# deadlocks3.net
KiCad netlist of a schematic drawn in EAGLE
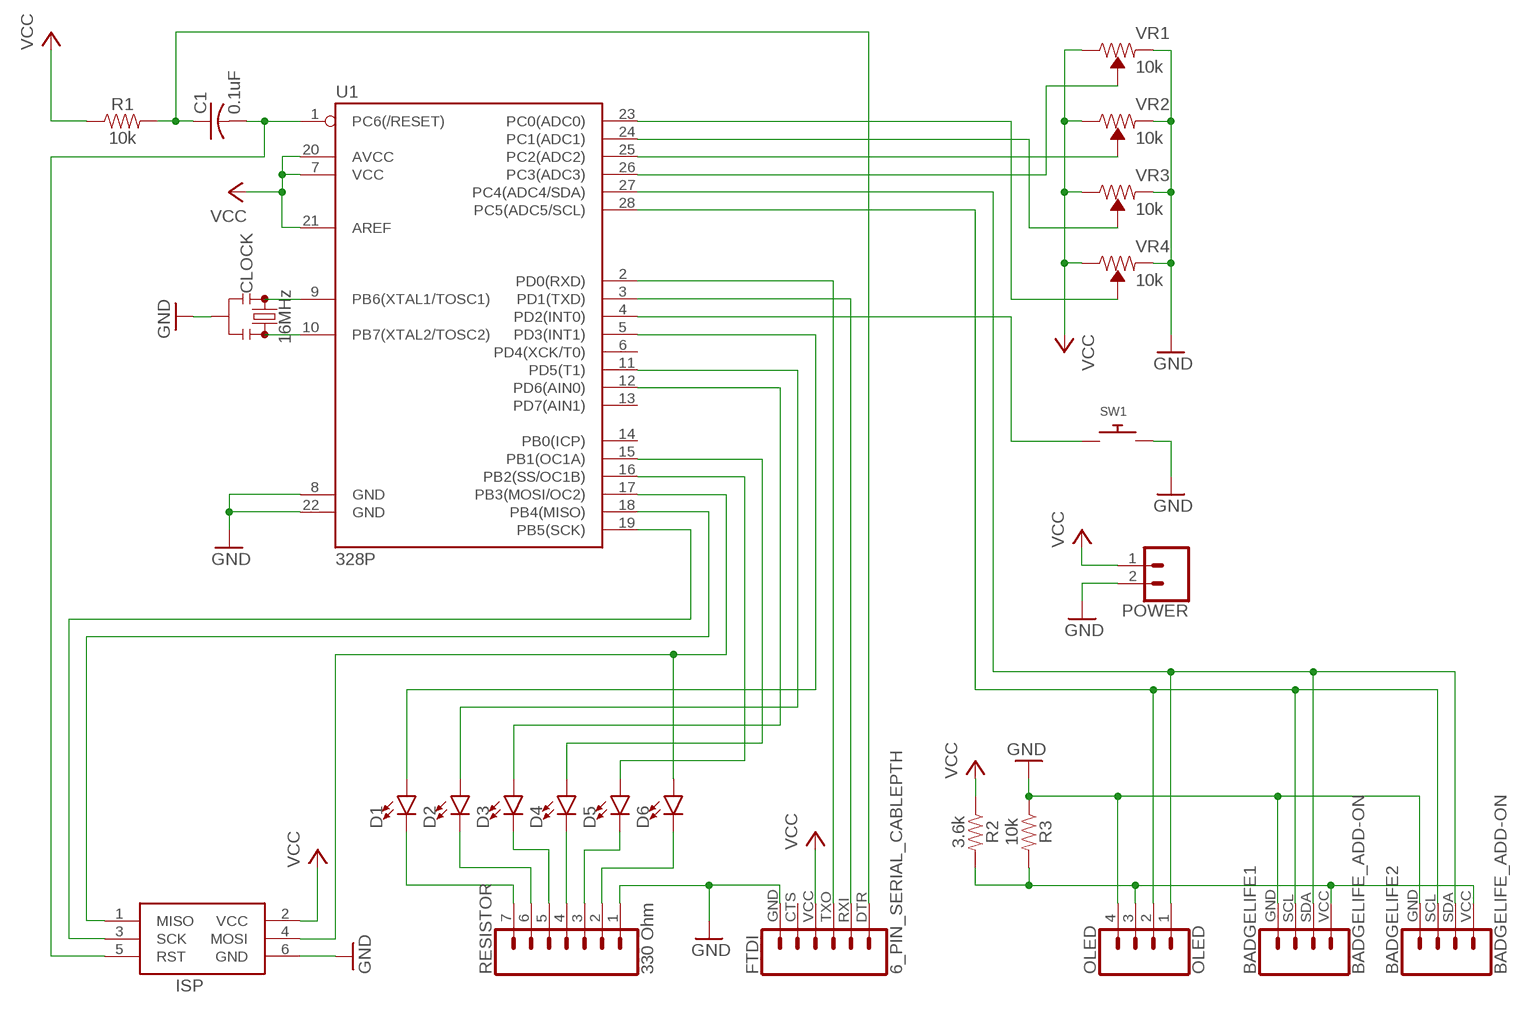
[diagram p0: schematic, sheet 1]

(export (version "E")
  (design (tool "Eeschema 10.0.6"))
  (components
    (comp (ref "BADGELIFE1")
      (value "BADGELIFE_ADD-ON")
      (footprint "eagle-import:BADGELIFE_ADD-ON")
      (libsource (lib "eagle-import") (part "BADGELIFE_ADD-ON"))
    )
    (comp (ref "BADGELIFE2")
      (value "BADGELIFE_ADD-ON")
      (footprint "eagle-import:BADGELIFE_ADD-ON")
      (libsource (lib "eagle-import") (part "BADGELIFE_ADD-ON"))
    )
    (comp (ref "C1")
      (value "0.1uF")
      (footprint "eagle-import:C025-024X044")
      (libsource (lib "eagle-import") (part "C-US025-024X044"))
    )
    (comp (ref "CLOCK")
      (value "16MHz")
      (footprint "eagle-import:RESONATOR-PTH-7.6X3.8")
      (libsource (lib "eagle-import") (part "RESONATORPTH-7.6X3.8"))
    )
    (comp (ref "D1")
      (value "LED5MM")
      (footprint "eagle-import:LED_5MM")
      (libsource (lib "eagle-import") (part "LED5MM"))
    )
    (comp (ref "D2")
      (value "LED5MM")
      (footprint "eagle-import:LED_5MM")
      (libsource (lib "eagle-import") (part "LED5MM"))
    )
    (comp (ref "D3")
      (value "LED5MM")
      (footprint "eagle-import:LED_5MM")
      (libsource (lib "eagle-import") (part "LED5MM"))
    )
    (comp (ref "D4")
      (value "LED5MM")
      (footprint "eagle-import:LED_5MM")
      (libsource (lib "eagle-import") (part "LED5MM"))
    )
    (comp (ref "D5")
      (value "LED5MM")
      (footprint "eagle-import:LED_5MM")
      (libsource (lib "eagle-import") (part "LED5MM"))
    )
    (comp (ref "D6")
      (value "LED5MM")
      (footprint "eagle-import:LED_5MM")
      (libsource (lib "eagle-import") (part "LED5MM"))
    )
    (comp (ref "FTDI")
      (value "6_PIN_SERIAL_CABLEPTH")
      (footprint "eagle-import:FTDI_BASIC")
      (libsource (lib "eagle-import") (part "6_PIN_SERIAL_CABLEPTH"))
    )
    (comp (ref "ISP")
      (value "AVRISP-6")
      (footprint "eagle-import:AVRISP")
      (libsource (lib "eagle-import") (part "AVRISP-6"))
    )
    (comp (ref "OLED")
      (value "OLED")
      (footprint "eagle-import:1X04")
      (libsource (lib "eagle-import") (part "CONN_04"))
    )
    (comp (ref "POWER")
      (value "CONN_02")
      (footprint "eagle-import:1X02")
      (libsource (lib "eagle-import") (part "CONN_02"))
    )
    (comp (ref "R1")
      (value "10k")
      (footprint "eagle-import:AXIAL-0.3")
      (libsource (lib "eagle-import") (part "10KOHM-HORIZ-1/4W-1%"))
    )
    (comp (ref "R2")
      (value "3.6k")
      (footprint "eagle-import:AXIAL-0.3")
      (libsource (lib "eagle-import") (part "10KOHM-HORIZ-1/4W-1%"))
    )
    (comp (ref "R3")
      (value "10k")
      (footprint "eagle-import:AXIAL-0.3")
      (libsource (lib "eagle-import") (part "10KOHM-HORIZ-1/4W-1%"))
    )
    (comp (ref "RESISTOR")
      (value "330 Ohm")
      (footprint "eagle-import:1X07")
      (libsource (lib "eagle-import") (part "CONN_07"))
    )
    (comp (ref "SW1")
      (value "SWITCH_PUSHBUTTONEVQ-PE")
      (footprint "eagle-import:TACT_PANA-EVQ")
      (libsource (lib "eagle-import") (part "SWITCH_PUSHBUTTONEVQ-PE"))
    )
    (comp (ref "U1")
      (value "328P")
      (footprint "eagle-import:DIP28")
      (libsource (lib "eagle-import") (part "ATMEGA328P_PDIP"))
    )
    (comp (ref "VR1")
      (value "10k")
      (footprint "eagle-import:TRIMPOT-PTH-3386U")
      (libsource (lib "eagle-import") (part "TRIMPOT-PTH-10MM-KNOB-1/2W-10%"))
    )
    (comp (ref "VR2")
      (value "10k")
      (footprint "eagle-import:TRIMPOT-PTH-3386U")
      (libsource (lib "eagle-import") (part "TRIMPOT-PTH-10MM-KNOB-1/2W-10%"))
    )
    (comp (ref "VR3")
      (value "10k")
      (footprint "eagle-import:TRIMPOT-PTH-3386U")
      (libsource (lib "eagle-import") (part "TRIMPOT-PTH-10MM-KNOB-1/2W-10%"))
    )
    (comp (ref "VR4")
      (value "10k")
      (footprint "eagle-import:TRIMPOT-PTH-3386U")
      (libsource (lib "eagle-import") (part "TRIMPOT-PTH-10MM-KNOB-1/2W-10%"))
    )
  )
  (nets
    (net (code "1") (name "GND") (class "Default")
      (node (ref "BADGELIFE1") (pin "GND") (pinfunction "4_GND") (pintype "passive"))
      (node (ref "BADGELIFE2") (pin "GND") (pinfunction "4_GND") (pintype "passive"))
      (node (ref "CLOCK") (pin "2") (pinfunction "2_2") (pintype "passive"))
      (node (ref "FTDI") (pin "GND") (pinfunction "6_GND") (pintype "passive"))
      (node (ref "ISP") (pin "6") (pinfunction "GND_6") (pintype "power_in"))
      (node (ref "OLED") (pin "4") (pinfunction "4_4") (pintype "passive"))
      (node (ref "POWER") (pin "2") (pinfunction "2_2") (pintype "passive"))
      (node (ref "R3") (pin "P$1") (pinfunction "1_P$1") (pintype "passive"))
      (node (ref "RESISTOR") (pin "1") (pinfunction "1_1") (pintype "passive"))
      (node (ref "SW1") (pin "P$2") (pinfunction "P$2_P$2") (pintype "passive"))
      (node (ref "U1") (pin "22") (pinfunction "GND_22") (pintype "bidirectional"))
      (node (ref "U1") (pin "8") (pinfunction "GND_8") (pintype "bidirectional"))
      (node (ref "VR1") (pin "1") (pinfunction "CCW_1") (pintype "passive"))
      (node (ref "VR2") (pin "1") (pinfunction "CCW_1") (pintype "passive"))
      (node (ref "VR3") (pin "1") (pinfunction "CCW_1") (pintype "passive"))
      (node (ref "VR4") (pin "1") (pinfunction "CCW_1") (pintype "passive"))
    )
    (net (code "2") (name "Net-(BADGELIFE1-1)") (class "Default")
      (node (ref "BADGELIFE1") (pin "VCC") (pinfunction "1_VCC") (pintype "passive"))
      (node (ref "BADGELIFE2") (pin "VCC") (pinfunction "1_VCC") (pintype "passive"))
      (node (ref "OLED") (pin "3") (pinfunction "3_3") (pintype "passive"))
      (node (ref "R2") (pin "P$2") (pinfunction "2_P$2") (pintype "passive"))
      (node (ref "R3") (pin "P$2") (pinfunction "2_P$2") (pintype "passive"))
    )
    (net (code "3") (name "Net-(BADGELIFE1-2)") (class "Default")
      (node (ref "BADGELIFE1") (pin "SDA") (pinfunction "2_SDA") (pintype "passive"))
      (node (ref "BADGELIFE2") (pin "SDA") (pinfunction "2_SDA") (pintype "passive"))
      (node (ref "OLED") (pin "1") (pinfunction "1_1") (pintype "passive"))
      (node (ref "U1") (pin "27") (pinfunction "PC4(ADC4/SDA)_27") (pintype "bidirectional"))
    )
    (net (code "4") (name "Net-(BADGELIFE1-3)") (class "Default")
      (node (ref "BADGELIFE1") (pin "SCL") (pinfunction "3_SCL") (pintype "passive"))
      (node (ref "BADGELIFE2") (pin "SCL") (pinfunction "3_SCL") (pintype "passive"))
      (node (ref "OLED") (pin "2") (pinfunction "2_2") (pintype "passive"))
      (node (ref "U1") (pin "28") (pinfunction "PC5(ADC5/SCL)_28") (pintype "bidirectional"))
    )
    (net (code "5") (name "Net-(D1-C)") (class "Default")
      (node (ref "D1") (pin "K") (pinfunction "C_K") (pintype "passive"))
      (node (ref "RESISTOR") (pin "7") (pinfunction "7_7") (pintype "passive"))
    )
    (net (code "6") (name "Net-(D2-C)") (class "Default")
      (node (ref "D2") (pin "K") (pinfunction "C_K") (pintype "passive"))
      (node (ref "RESISTOR") (pin "6") (pinfunction "6_6") (pintype "passive"))
    )
    (net (code "7") (name "Net-(D3-C)") (class "Default")
      (node (ref "D3") (pin "K") (pinfunction "C_K") (pintype "passive"))
      (node (ref "RESISTOR") (pin "5") (pinfunction "5_5") (pintype "passive"))
    )
    (net (code "8") (name "Net-(D4-C)") (class "Default")
      (node (ref "D4") (pin "K") (pinfunction "C_K") (pintype "passive"))
      (node (ref "RESISTOR") (pin "4") (pinfunction "4_4") (pintype "passive"))
    )
    (net (code "9") (name "Net-(D5-C)") (class "Default")
      (node (ref "D5") (pin "K") (pinfunction "C_K") (pintype "passive"))
      (node (ref "RESISTOR") (pin "3") (pinfunction "3_3") (pintype "passive"))
    )
    (net (code "10") (name "Net-(D6-C)") (class "Default")
      (node (ref "D6") (pin "K") (pinfunction "C_K") (pintype "passive"))
      (node (ref "RESISTOR") (pin "2") (pinfunction "2_2") (pintype "passive"))
    )
    (net (code "11") (name "Net-(FTDI-1)") (class "Default")
      (node (ref "C1") (pin "1") (pinfunction "1_1") (pintype "passive"))
      (node (ref "FTDI") (pin "DTR") (pinfunction "1_DTR") (pintype "passive"))
      (node (ref "R1") (pin "P$2") (pinfunction "2_P$2") (pintype "passive"))
    )
    (net (code "12") (name "Net-(FTDI-2)") (class "Default")
      (node (ref "FTDI") (pin "RXI") (pinfunction "2_RXI") (pintype "passive"))
      (node (ref "U1") (pin "3") (pinfunction "PD1(TXD)_3") (pintype "bidirectional"))
    )
    (net (code "13") (name "Net-(FTDI-3)") (class "Default")
      (node (ref "FTDI") (pin "TXO") (pinfunction "3_TXO") (pintype "passive"))
      (node (ref "U1") (pin "2") (pinfunction "PD0(RXD)_2") (pintype "bidirectional"))
    )
    (net (code "14") (name "Net-(ISP-MISO)") (class "Default")
      (node (ref "ISP") (pin "1") (pinfunction "MISO_1") (pintype "input"))
      (node (ref "U1") (pin "18") (pinfunction "PB4(MISO)_18") (pintype "bidirectional"))
    )
    (net (code "15") (name "Net-(ISP-MOSI)") (class "Default")
      (node (ref "D6") (pin "A") (pinfunction "A_A") (pintype "passive"))
      (node (ref "ISP") (pin "4") (pinfunction "MOSI_4") (pintype "output"))
      (node (ref "U1") (pin "17") (pinfunction "PB3(MOSI/OC2)_17") (pintype "bidirectional"))
    )
    (net (code "16") (name "Net-(ISP-RST)") (class "Default")
      (node (ref "C1") (pin "2") (pinfunction "2_2") (pintype "passive"))
      (node (ref "ISP") (pin "5") (pinfunction "RST_5") (pintype "output"))
      (node (ref "U1") (pin "1") (pinfunction "PC6(/RESET)_1") (pintype "bidirectional"))
    )
    (net (code "17") (name "Net-(ISP-SCK)") (class "Default")
      (node (ref "ISP") (pin "3") (pinfunction "SCK_3") (pintype "output"))
      (node (ref "U1") (pin "19") (pinfunction "PB5(SCK)_19") (pintype "bidirectional"))
    )
    (net (code "18") (name "Net-(U1-PB1(OC1A))") (class "Default")
      (node (ref "D4") (pin "A") (pinfunction "A_A") (pintype "passive"))
      (node (ref "U1") (pin "15") (pinfunction "PB1(OC1A)_15") (pintype "bidirectional"))
    )
    (net (code "19") (name "Net-(U1-PB2(SS{slash}OC1B))") (class "Default")
      (node (ref "D5") (pin "A") (pinfunction "A_A") (pintype "passive"))
      (node (ref "U1") (pin "16") (pinfunction "PB2(SS/OC1B)_16") (pintype "bidirectional"))
    )
    (net (code "20") (name "Net-(U1-PB6(XTAL1{slash}TOSC1))") (class "Default")
      (node (ref "CLOCK") (pin "1") (pinfunction "1_1") (pintype "passive"))
      (node (ref "U1") (pin "9") (pinfunction "PB6(XTAL1/TOSC1)_9") (pintype "bidirectional"))
    )
    (net (code "21") (name "Net-(U1-PB7(XTAL2{slash}TOSC2))") (class "Default")
      (node (ref "CLOCK") (pin "3") (pinfunction "3_3") (pintype "passive"))
      (node (ref "U1") (pin "10") (pinfunction "PB7(XTAL2/TOSC2)_10") (pintype "bidirectional"))
    )
    (net (code "22") (name "Net-(U1-PC0(ADC0))") (class "Default")
      (node (ref "U1") (pin "23") (pinfunction "PC0(ADC0)_23") (pintype "bidirectional"))
      (node (ref "VR4") (pin "2") (pinfunction "WIPER_2") (pintype "passive"))
    )
    (net (code "23") (name "Net-(U1-PC1(ADC1))") (class "Default")
      (node (ref "U1") (pin "24") (pinfunction "PC1(ADC1)_24") (pintype "bidirectional"))
      (node (ref "VR3") (pin "2") (pinfunction "WIPER_2") (pintype "passive"))
    )
    (net (code "24") (name "Net-(U1-PC2(ADC2))") (class "Default")
      (node (ref "U1") (pin "25") (pinfunction "PC2(ADC2)_25") (pintype "bidirectional"))
      (node (ref "VR2") (pin "2") (pinfunction "WIPER_2") (pintype "passive"))
    )
    (net (code "25") (name "Net-(U1-PC3(ADC3))") (class "Default")
      (node (ref "U1") (pin "26") (pinfunction "PC3(ADC3)_26") (pintype "bidirectional"))
      (node (ref "VR1") (pin "2") (pinfunction "WIPER_2") (pintype "passive"))
    )
    (net (code "26") (name "Net-(U1-PD2(INT0))") (class "Default")
      (node (ref "SW1") (pin "P$1") (pinfunction "P$1_P$1") (pintype "passive"))
      (node (ref "U1") (pin "4") (pinfunction "PD2(INT0)_4") (pintype "bidirectional"))
    )
    (net (code "27") (name "Net-(U1-PD3(INT1))") (class "Default")
      (node (ref "D1") (pin "A") (pinfunction "A_A") (pintype "passive"))
      (node (ref "U1") (pin "5") (pinfunction "PD3(INT1)_5") (pintype "bidirectional"))
    )
    (net (code "28") (name "Net-(U1-PD5(T1))") (class "Default")
      (node (ref "D2") (pin "A") (pinfunction "A_A") (pintype "passive"))
      (node (ref "U1") (pin "11") (pinfunction "PD5(T1)_11") (pintype "bidirectional"))
    )
    (net (code "29") (name "Net-(U1-PD6(AIN0))") (class "Default")
      (node (ref "D3") (pin "A") (pinfunction "A_A") (pintype "passive"))
      (node (ref "U1") (pin "12") (pinfunction "PD6(AIN0)_12") (pintype "bidirectional"))
    )
    (net (code "30") (name "VCC") (class "Default")
      (node (ref "FTDI") (pin "VCC") (pinfunction "4_VCC") (pintype "passive"))
      (node (ref "ISP") (pin "2") (pinfunction "VCC_2") (pintype "power_in"))
      (node (ref "POWER") (pin "1") (pinfunction "1_1") (pintype "passive"))
      (node (ref "R1") (pin "P$1") (pinfunction "1_P$1") (pintype "passive"))
      (node (ref "R2") (pin "P$1") (pinfunction "1_P$1") (pintype "passive"))
      (node (ref "U1") (pin "20") (pinfunction "AVCC_20") (pintype "bidirectional"))
      (node (ref "U1") (pin "21") (pinfunction "AREF_21") (pintype "bidirectional"))
      (node (ref "U1") (pin "7") (pinfunction "VCC_7") (pintype "bidirectional"))
      (node (ref "VR1") (pin "3") (pinfunction "CW_3") (pintype "passive"))
      (node (ref "VR2") (pin "3") (pinfunction "CW_3") (pintype "passive"))
      (node (ref "VR3") (pin "3") (pinfunction "CW_3") (pintype "passive"))
      (node (ref "VR4") (pin "3") (pinfunction "CW_3") (pintype "passive"))
    )
    (net (code "31") (name "unconnected-(FTDI-5-PadCTS)") (class "Default")
      (node (ref "FTDI") (pin "CTS") (pinfunction "5_CTS") (pintype "passive"))
    )
    (net (code "32") (name "unconnected-(U1-PB0(ICP)-Pad14)") (class "Default")
      (node (ref "U1") (pin "14") (pinfunction "PB0(ICP)_14") (pintype "bidirectional"))
    )
    (net (code "33") (name "unconnected-(U1-PD4(XCK{slash}T0)-Pad6)") (class "Default")
      (node (ref "U1") (pin "6") (pinfunction "PD4(XCK/T0)_6") (pintype "bidirectional"))
    )
    (net (code "34") (name "unconnected-(U1-PD7(AIN1)-Pad13)") (class "Default")
      (node (ref "U1") (pin "13") (pinfunction "PD7(AIN1)_13") (pintype "bidirectional"))
    )
  )
)
